# SparkX_Micro_NFC_RFID_Tag.net
KiCad netlist of a schematic drawn in EAGLE
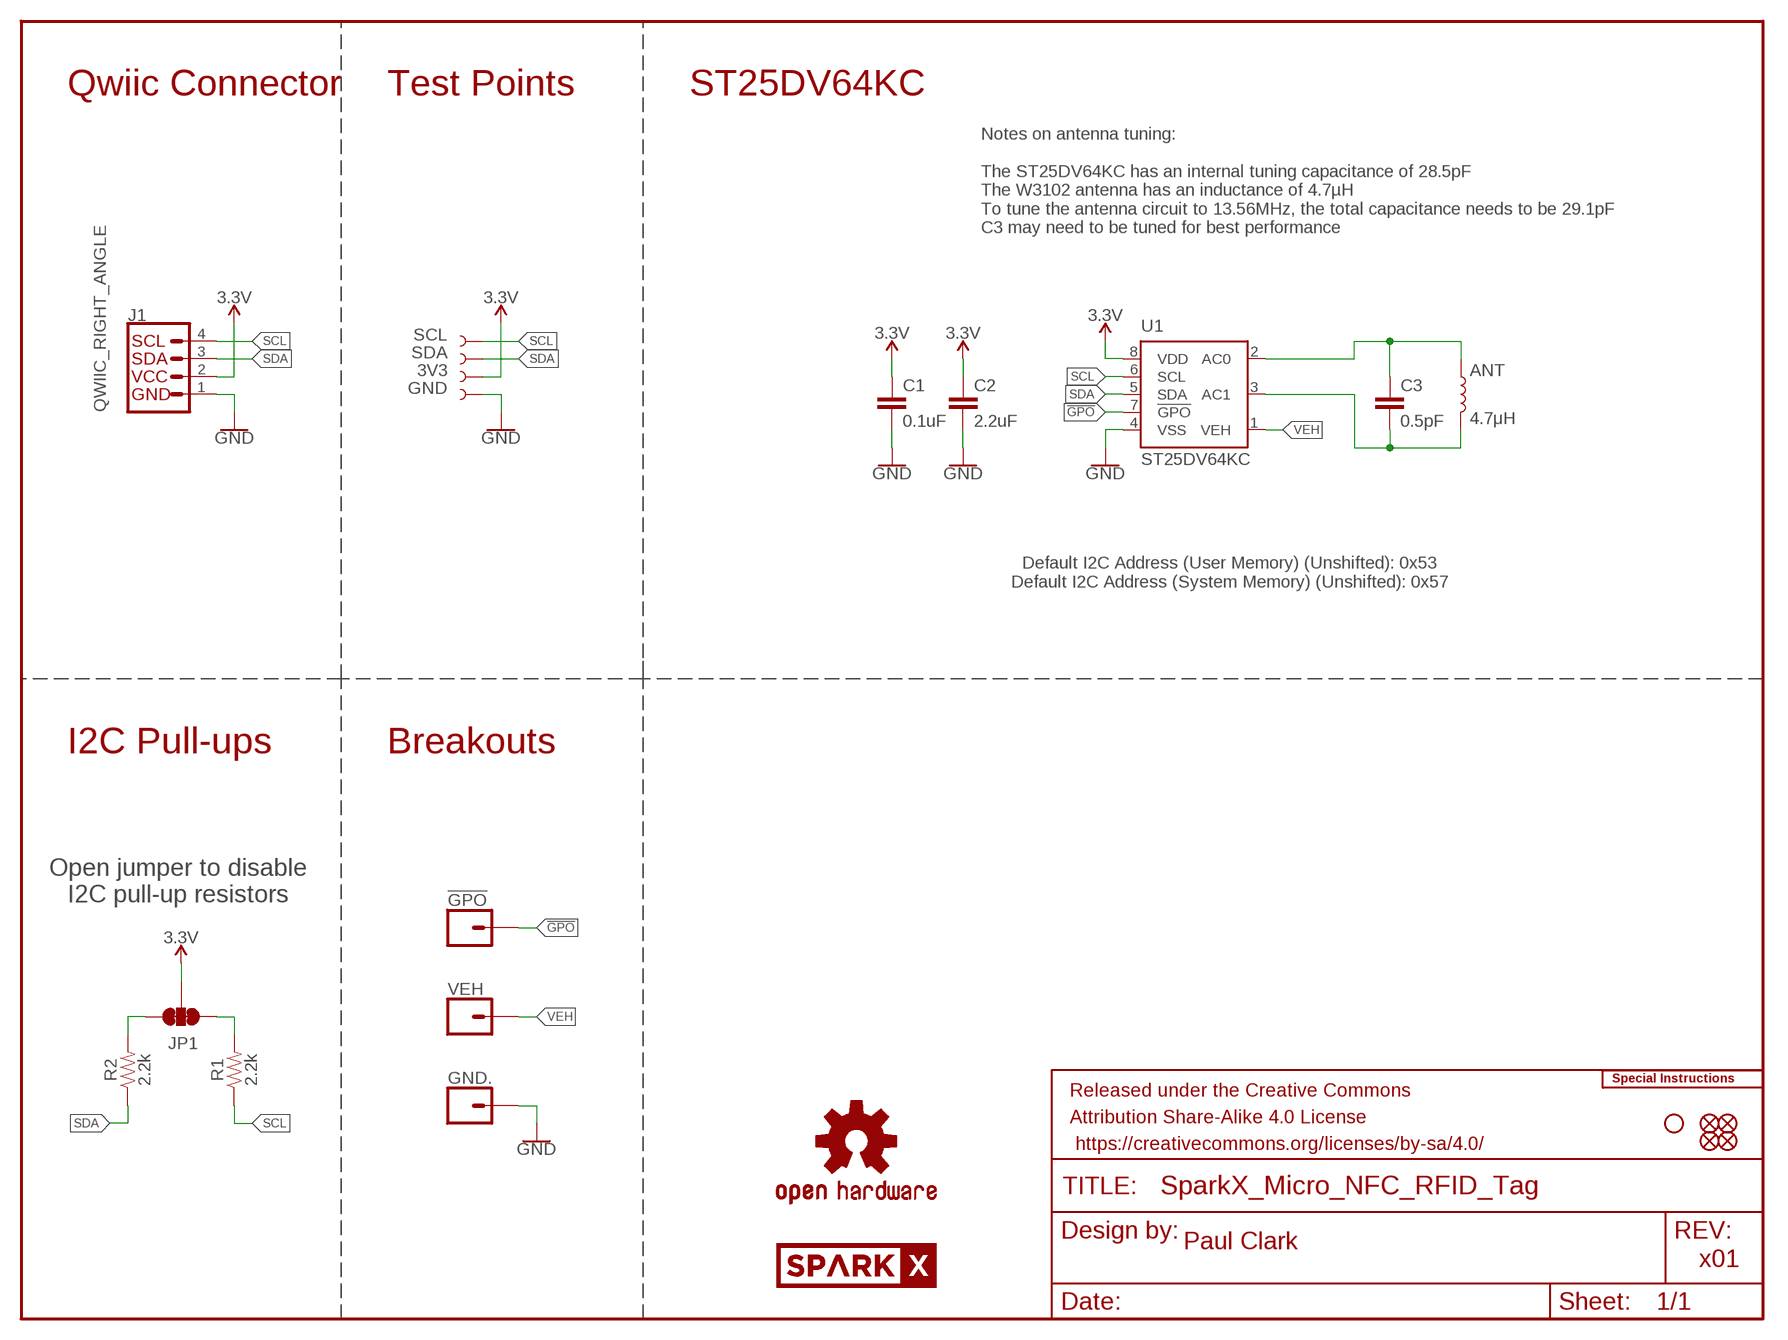
[diagram p0: schematic, sheet 1]

(export (version "E")
  (design (tool "Eeschema 10.0.6"))
  (components
    (comp (ref "!GPO!")
      (value "CONN_01_1MM")
      (footprint "eagle-import:1X01_1MM_NO_SILK")
      (libsource (lib "eagle-import") (part "CONN_01_1MM"))
    )
    (comp (ref "3V3")
      (value "TEST-POINT3")
      (footprint "eagle-import:PAD.03X.03")
      (libsource (lib "eagle-import") (part "TEST-POINT3"))
    )
    (comp (ref "ANT")
      (value "4.7μH")
      (footprint "eagle-import:W3102")
      (libsource (lib "eagle-import") (part "RFID_ANTENNA_W3102"))
    )
    (comp (ref "C1")
      (value "0.1uF")
      (footprint "eagle-import:0402-TIGHT")
      (libsource (lib "eagle-import") (part "0.1UF-0402T-6.3V-10%-X7R"))
    )
    (comp (ref "C2")
      (value "2.2uF")
      (footprint "eagle-import:0402-TIGHT")
      (libsource (lib "eagle-import") (part "2.2UF-0402_TIGHT-10V-10%-X5R"))
    )
    (comp (ref "C3")
      (value "0.5pF")
      (footprint "eagle-import:0402-TIGHT")
      (libsource (lib "eagle-import") (part "0.5PF-0402_TIGHT-50V-PM0.05PF-NP0"))
    )
    (comp (ref "FD1")
      (value "FIDUCIALUFIDUCIAL")
      (footprint "eagle-import:FIDUCIAL-MICRO")
      (libsource (lib "eagle-import") (part "FIDUCIALUFIDUCIAL"))
    )
    (comp (ref "FD2")
      (value "FIDUCIALUFIDUCIAL")
      (footprint "eagle-import:FIDUCIAL-MICRO")
      (libsource (lib "eagle-import") (part "FIDUCIALUFIDUCIAL"))
    )
    (comp (ref "FD3")
      (value "FIDUCIALUFIDUCIAL")
      (footprint "eagle-import:FIDUCIAL-MICRO")
      (libsource (lib "eagle-import") (part "FIDUCIALUFIDUCIAL"))
    )
    (comp (ref "FD4")
      (value "FIDUCIALUFIDUCIAL")
      (footprint "eagle-import:FIDUCIAL-MICRO")
      (libsource (lib "eagle-import") (part "FIDUCIALUFIDUCIAL"))
    )
    (comp (ref "FRAME2")
      (value "FRAME-LETTER")
      (footprint "eagle-import:CREATIVE_COMMONS")
      (libsource (lib "eagle-import") (part "FRAME-LETTER"))
    )
    (comp (ref "GND")
      (value "TEST-POINT3")
      (footprint "eagle-import:PAD.03X.03")
      (libsource (lib "eagle-import") (part "TEST-POINT3"))
    )
    (comp (ref "GND.")
      (value "CONN_01_1MM")
      (footprint "eagle-import:1X01_1MM_NO_SILK")
      (libsource (lib "eagle-import") (part "CONN_01_1MM"))
    )
    (comp (ref "H1")
      (value "STAND-OFFTIGHT")
      (footprint "eagle-import:STAND-OFF-TIGHT")
      (libsource (lib "eagle-import") (part "STAND-OFFTIGHT"))
    )
    (comp (ref "J1")
      (value "QWIIC_RIGHT_ANGLE")
      (footprint "eagle-import:JST04_1MM_RA")
      (libsource (lib "eagle-import") (part "QWIIC_CONNECTORJS-1MM"))
    )
    (comp (ref "JP1")
      (value "JUMPER-SMT_3_2-NC_TRACE_SILK")
      (footprint "eagle-import:SMT-JUMPER_3_2-NC_TRACE_SILK")
      (libsource (lib "eagle-import") (part "JUMPER-SMT_3_2-NC_TRACE_SILK"))
    )
    (comp (ref "LOGO1")
      (value "SPECIAL_INSTRUCTIONS-ORDERING")
      (footprint "eagle-import:ORDERING_INSTRUCTIONS")
      (libsource (lib "eagle-import") (part "SPECIAL_INSTRUCTIONS-ORDERING"))
    )
    (comp (ref "LOGO2")
      (value "OSHW-LOGOMINI")
      (footprint "eagle-import:OSHW-LOGO-MINI")
      (libsource (lib "eagle-import") (part "OSHW-LOGOMINI"))
    )
    (comp (ref "R1")
      (value "2.2k")
      (footprint "eagle-import:0402-TIGHT")
      (libsource (lib "eagle-import") (part "2.2KOHM-0402T-1/16W-1%"))
    )
    (comp (ref "R2")
      (value "2.2k")
      (footprint "eagle-import:0402-TIGHT")
      (libsource (lib "eagle-import") (part "2.2KOHM-0402T-1/16W-1%"))
    )
    (comp (ref "SCL")
      (value "TEST-POINT3")
      (footprint "eagle-import:PAD.03X.03")
      (libsource (lib "eagle-import") (part "TEST-POINT3"))
    )
    (comp (ref "SDA")
      (value "TEST-POINT3")
      (footprint "eagle-import:PAD.03X.03")
      (libsource (lib "eagle-import") (part "TEST-POINT3"))
    )
    (comp (ref "U$1")
      (value "SPARKX-LOGO2")
      (footprint "eagle-import:SPARKX-TINY")
      (libsource (lib "eagle-import") (part "SPARKX-LOGO2"))
    )
    (comp (ref "U1")
      (value "ST25DV64KC")
      (footprint "eagle-import:SO08")
      (libsource (lib "eagle-import") (part "ST25DV64KC"))
    )
    (comp (ref "VEH")
      (value "CONN_01_1MM")
      (footprint "eagle-import:1X01_1MM_NO_SILK")
      (libsource (lib "eagle-import") (part "CONN_01_1MM"))
    )
  )
  (nets
    (net (code "1") (name "/~{GPO}") (class "Default")
      (node (ref "!GPO!") (pin "1") (pinfunction "1_1") (pintype "passive"))
      (node (ref "U1") (pin "7") (pinfunction "~{GPO}_7") (pintype "output"))
    )
    (net (code "2") (name "3.3V") (class "Default")
      (node (ref "3V3") (pin "1") (pinfunction "1_1") (pintype "bidirectional"))
      (node (ref "C1") (pin "1") (pinfunction "1_1") (pintype "passive"))
      (node (ref "C2") (pin "1") (pinfunction "1_1") (pintype "passive"))
      (node (ref "J1") (pin "2") (pinfunction "2_2") (pintype "power_in"))
      (node (ref "JP1") (pin "2") (pinfunction "2_2") (pintype "passive"))
      (node (ref "U1") (pin "8") (pinfunction "VDD_8") (pintype "power_in"))
    )
    (net (code "3") (name "GND") (class "Default")
      (node (ref "C1") (pin "2") (pinfunction "2_2") (pintype "passive"))
      (node (ref "C2") (pin "2") (pinfunction "2_2") (pintype "passive"))
      (node (ref "GND") (pin "1") (pinfunction "1_1") (pintype "bidirectional"))
      (node (ref "GND.") (pin "1") (pinfunction "1_1") (pintype "passive"))
      (node (ref "J1") (pin "1") (pinfunction "1_1") (pintype "power_in"))
      (node (ref "U1") (pin "4") (pinfunction "VSS_4") (pintype "power_in"))
    )
    (net (code "4") (name "Net-(JP1-Pad1)") (class "Default")
      (node (ref "JP1") (pin "1") (pinfunction "1_1") (pintype "passive"))
      (node (ref "R1") (pin "2") (pinfunction "2_2") (pintype "passive"))
    )
    (net (code "5") (name "Net-(JP1-Pad3)") (class "Default")
      (node (ref "JP1") (pin "3") (pinfunction "3_3") (pintype "passive"))
      (node (ref "R2") (pin "2") (pinfunction "2_2") (pintype "passive"))
    )
    (net (code "6") (name "Net-(U1-AC0)") (class "Default")
      (node (ref "ANT") (pin "1") (pinfunction "1_1") (pintype "passive"))
      (node (ref "C3") (pin "1") (pinfunction "1_1") (pintype "passive"))
      (node (ref "U1") (pin "2") (pinfunction "AC0_2") (pintype "bidirectional"))
    )
    (net (code "7") (name "Net-(U1-AC1)") (class "Default")
      (node (ref "ANT") (pin "2") (pinfunction "2_2") (pintype "passive"))
      (node (ref "C3") (pin "2") (pinfunction "2_2") (pintype "passive"))
      (node (ref "U1") (pin "3") (pinfunction "AC1_3") (pintype "bidirectional"))
    )
    (net (code "8") (name "SCL") (class "Default")
      (node (ref "J1") (pin "4") (pinfunction "4_4") (pintype "passive"))
      (node (ref "R1") (pin "1") (pinfunction "1_1") (pintype "passive"))
      (node (ref "SCL") (pin "1") (pinfunction "1_1") (pintype "bidirectional"))
      (node (ref "U1") (pin "6") (pinfunction "SCL_6") (pintype "bidirectional"))
    )
    (net (code "9") (name "SDA") (class "Default")
      (node (ref "J1") (pin "3") (pinfunction "3_3") (pintype "passive"))
      (node (ref "R2") (pin "1") (pinfunction "1_1") (pintype "passive"))
      (node (ref "SDA") (pin "1") (pinfunction "1_1") (pintype "bidirectional"))
      (node (ref "U1") (pin "5") (pinfunction "SDA_5") (pintype "bidirectional"))
    )
    (net (code "10") (name "VEH") (class "Default")
      (node (ref "U1") (pin "1") (pinfunction "VEH_1") (pintype "power_in"))
      (node (ref "VEH") (pin "1") (pinfunction "1_1") (pintype "passive"))
    )
  )
)
